# precVref.net
KiCad netlist of a schematic drawn in EAGLE
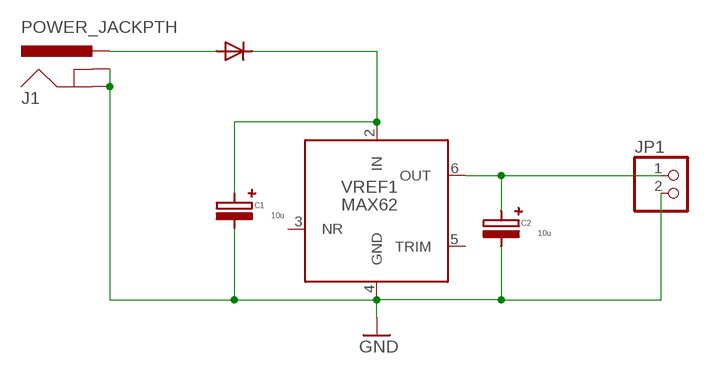
[diagram p0: schematic, sheet 1]

(export (version "E")
  (design (tool "Eeschema 10.0.6"))
  (components
    (comp (ref "C1")
      (value "10u")
      (footprint "eagle-import:CPOL1,5_5")
      (libsource (lib "eagle-import") (part "C-POL1.5/5"))
    )
    (comp (ref "C2")
      (value "10u")
      (footprint "eagle-import:CPOL1,5_5")
      (libsource (lib "eagle-import") (part "C-POL1.5/5"))
    )
    (comp (ref "D1")
      (value "D7/2X5")
      (footprint "eagle-import:DO-41")
      (libsource (lib "eagle-import") (part "D7/2X5"))
    )
    (comp (ref "J1")
      (value "POWER_JACKPTH")
      (footprint "eagle-import:POWER_JACK_PTH")
      (libsource (lib "eagle-import") (part "POWER_JACKPTH"))
    )
    (comp (ref "JP1")
      (value "PINHD-1X2")
      (footprint "eagle-import:1X02")
      (libsource (lib "eagle-import") (part "PINHD-1X2"))
    )
    (comp (ref "VREF1")
      (value "MAX62")
      (footprint "eagle-import:SOIC-8")
      (libsource (lib "eagle-import") (part "MAX62"))
    )
  )
  (nets
    (net (code "1") (name "GND") (class "Default")
      (node (ref "C1") (pin "P$1") (pinfunction "NEG_P$1") (pintype "bidirectional"))
      (node (ref "C2") (pin "P$1") (pinfunction "NEG_P$1") (pintype "bidirectional"))
      (node (ref "J1") (pin "GND") (pinfunction "GND_GND") (pintype "bidirectional"))
      (node (ref "J1") (pin "GNDBREAK") (pinfunction "GNDBREAK_GNDBREAK") (pintype "bidirectional"))
      (node (ref "JP1") (pin "2") (pinfunction "2_2") (pintype "passive"))
      (node (ref "VREF1") (pin "4") (pinfunction "GND_4") (pintype "bidirectional"))
    )
    (net (code "2") (name "Net-(C1-POS)") (class "Default")
      (node (ref "C1") (pin "P$2") (pinfunction "POS_P$2") (pintype "bidirectional"))
      (node (ref "D1") (pin "CATHODE") (pinfunction "CATHODE_CATHODE") (pintype "bidirectional"))
      (node (ref "VREF1") (pin "2") (pinfunction "IN_2") (pintype "bidirectional"))
    )
    (net (code "3") (name "Net-(C2-POS)") (class "Default")
      (node (ref "C2") (pin "P$2") (pinfunction "POS_P$2") (pintype "bidirectional"))
      (node (ref "JP1") (pin "1") (pinfunction "1_1") (pintype "passive"))
      (node (ref "VREF1") (pin "6") (pinfunction "OUT_6") (pintype "bidirectional"))
    )
    (net (code "4") (name "Net-(D1-PadANODE)") (class "Default")
      (node (ref "D1") (pin "ANODE") (pinfunction "ANODE_ANODE") (pintype "bidirectional"))
      (node (ref "J1") (pin "PWR") (pinfunction "PWR_PWR") (pintype "bidirectional"))
    )
    (net (code "5") (name "unconnected-(VREF1-NR-Pad3)") (class "Default")
      (node (ref "VREF1") (pin "3") (pinfunction "NR_3") (pintype "bidirectional"))
    )
    (net (code "6") (name "unconnected-(VREF1-TRIM-Pad5)") (class "Default")
      (node (ref "VREF1") (pin "5") (pinfunction "TRIM_5") (pintype "bidirectional"))
    )
  )
)
